# PWRInput.net
KiCad netlist of a schematic drawn in Altium Designer
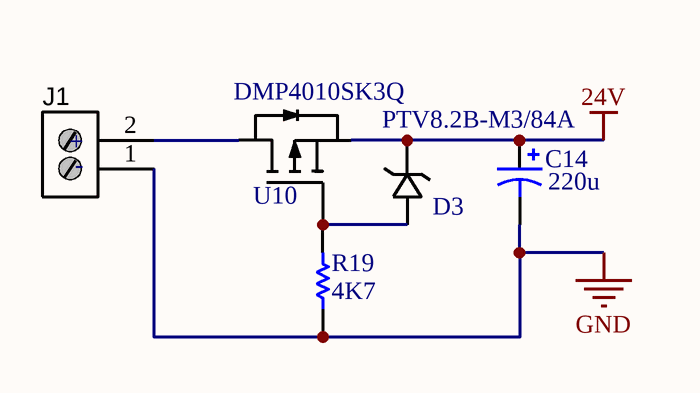
[diagram p0: PWRInput.SchDoc]

(export (version "E")
  (design (tool "Eeschema 10.0.6"))
  (components
    (comp (ref "C14")
      (value "220u")
      (footprint "CAP_ELEC_SIZE_G")
      (description "Polarized Capacitor (Radial)")
      (fields (field (name "Comment") "Cap Pol1") (field (name "PUBLISHER") "Altium Limited"))
      (libsource (lib "Miscellaneous Devices") (part "Cap Pol1"))
    )
    (comp (ref "D3")
      (value "PTV8.2B-M3/84A")
      (footprint "DO-220AA")
      (description "zener diode, Surface Mount Power Voltage-Regulating Diodes")
      (fields (field (name "MANUFACTURER") "Vishay"))
      (libsource (lib "IOBoard_Low") (part "PTV8.2B-M3/84A"))
    )
    (comp (ref "J1")
      (value "Stackable ScrewTerm")
      (footprint "2P_PCB_TERM")
      (description "Terminal Block Screw Type THT 2-Position 3.81mm pitch")
      (libsource (lib "IOBoard_Low") (part "2P_ScrewTerm_90S_3.81MM"))
    )
    (comp (ref "R19")
      (value "4K7")
      (footprint "RESC1608X55N")
      (description "Resistor")
      (fields (field (name "Comment") "Res1") (field (name "PUBLISHER") "Altium Limited"))
      (libsource (lib "IOBoard_Low") (part "Res1"))
    )
    (comp (ref "U10")
      (value "DMP4010SK3Q")
      (footprint "TO-252")
      (libsource (lib "IOBoard_Low") (part "DMP4010SK3Q"))
    )
  )
  (nets
    (net (code "1") (name "24V") (class "Default")
      (node (ref "C14") (pin "1") (pinfunction "1_1") (pintype "passive"))
      (node (ref "D3") (pin "K") (pinfunction "K_K") (pintype "passive"))
      (node (ref "U10") (pin "3") (pinfunction "S_3") (pintype "passive"))
    )
    (net (code "2") (name "GND") (class "Default")
      (node (ref "C14") (pin "2") (pinfunction "2_2") (pintype "passive"))
      (node (ref "J1") (pin "1") (pinfunction "1_1") (pintype "passive"))
      (node (ref "R19") (pin "1") (pinfunction "1_1") (pintype "passive"))
    )
    (net (code "3") (name "Net-(U10-D)") (class "Default")
      (node (ref "J1") (pin "2") (pinfunction "2_2") (pintype "passive"))
      (node (ref "U10") (pin "4") (pinfunction "D_4") (pintype "passive"))
    )
    (net (code "4") (name "Net-(U10-G)") (class "Default")
      (node (ref "D3") (pin "A") (pinfunction "A_A") (pintype "passive"))
      (node (ref "R19") (pin "2") (pinfunction "2_2") (pintype "passive"))
      (node (ref "U10") (pin "1") (pinfunction "G_1") (pintype "passive"))
    )
  )
)
